# v1.net
KiCad netlist of a schematic drawn in EAGLE
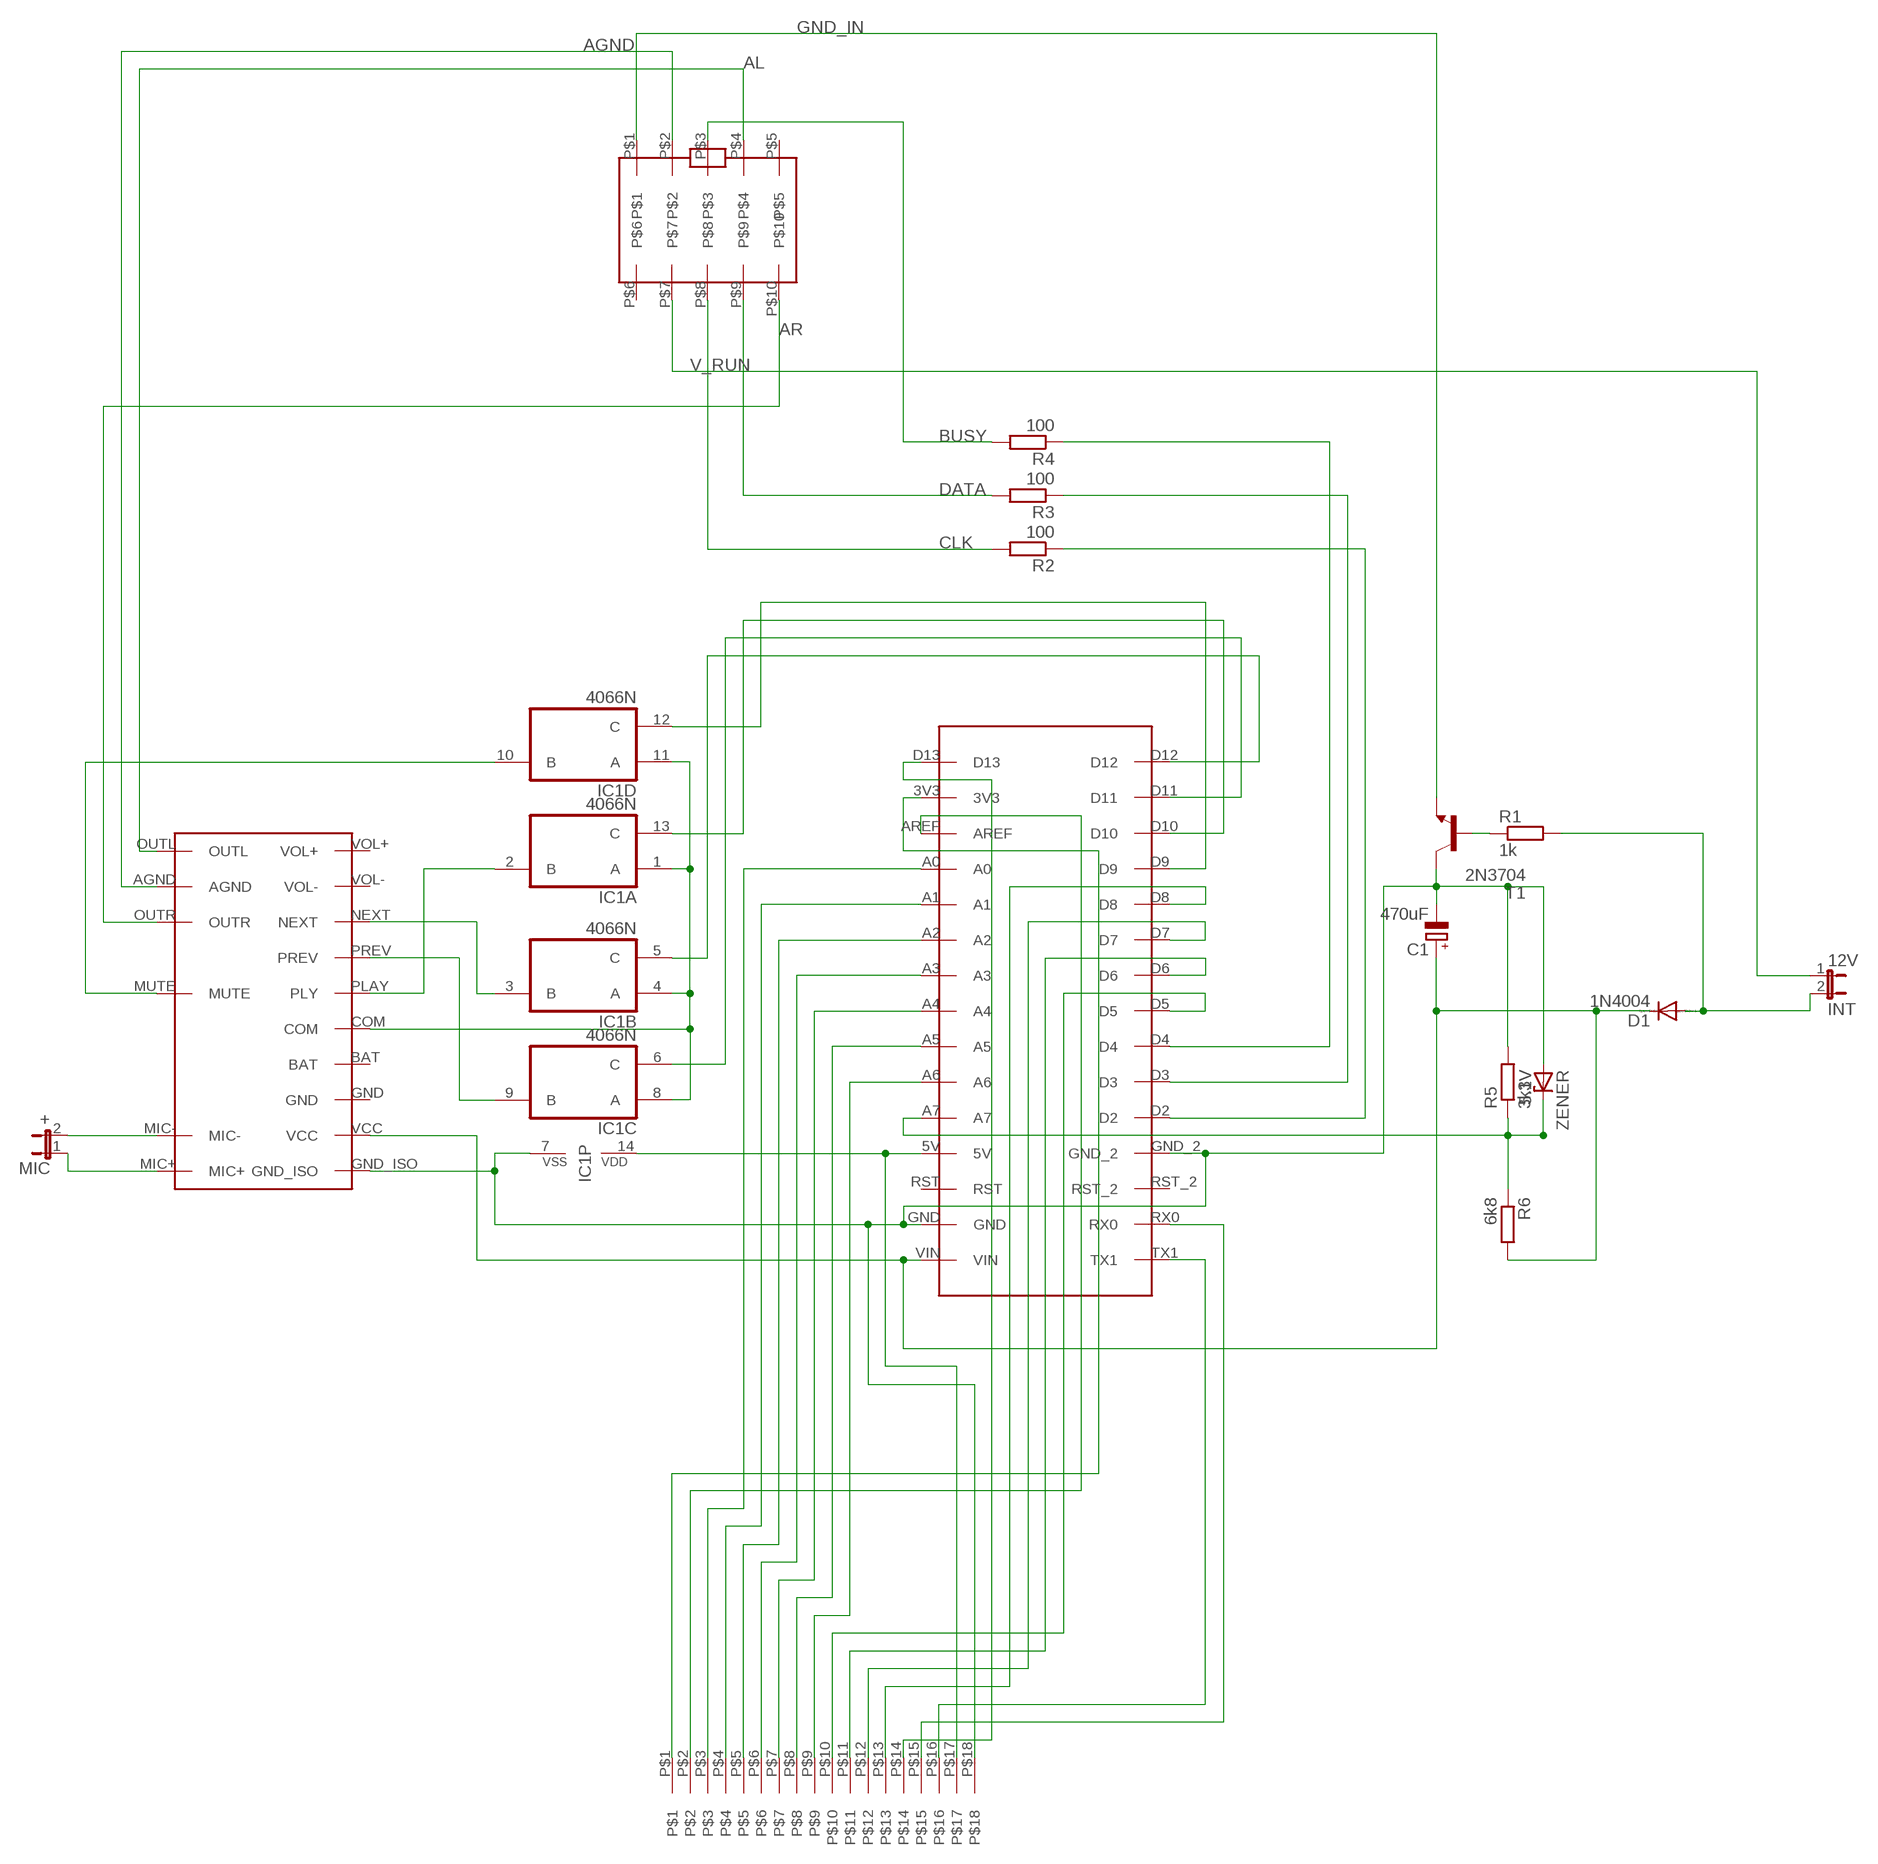
[diagram p0: schematic, sheet 1]

(export (version "E")
  (design (tool "Eeschema 10.0.6"))
  (components
    (comp (ref "12V")
      (value "INT")
      (footprint "eagle-import:JP1")
      (libsource (lib "eagle-import") (part "JP1E"))
    )
    (comp (ref "C1")
      (value "470uF")
      (footprint "eagle-import:E3,5-8")
      (libsource (lib "eagle-import") (part "CPOL-EUE3.5-8"))
    )
    (comp (ref "D1")
      (value "1N4004")
      (footprint "eagle-import:DO41-10")
      (libsource (lib "eagle-import") (part "1N4004"))
    )
    (comp (ref "IC1")
      (value "4066N")
      (footprint "eagle-import:DIL14")
      (libsource (lib "eagle-import") (part "4066N"))
    )
    (comp (ref "MIC")
      (value "+")
      (footprint "eagle-import:JP1")
      (libsource (lib "eagle-import") (part "JP1E"))
    )
    (comp (ref "R1")
      (value "1k")
      (footprint "eagle-import:0207_10")
      (libsource (lib "eagle-import") (part "R-EU_0207/10"))
    )
    (comp (ref "R2")
      (value "100")
      (footprint "eagle-import:0207_10")
      (libsource (lib "eagle-import") (part "R-EU_0207/10"))
    )
    (comp (ref "R3")
      (value "100")
      (footprint "eagle-import:0207_10")
      (libsource (lib "eagle-import") (part "R-EU_0207/10"))
    )
    (comp (ref "R4")
      (value "100")
      (footprint "eagle-import:0207_10")
      (libsource (lib "eagle-import") (part "R-EU_0207/10"))
    )
    (comp (ref "R5")
      (value "3k3")
      (footprint "eagle-import:0207_10")
      (libsource (lib "eagle-import") (part "R-EU_0207/10"))
    )
    (comp (ref "R6")
      (value "6k8")
      (footprint "eagle-import:0207_10")
      (libsource (lib "eagle-import") (part "R-EU_0207/10"))
    )
    (comp (ref "T1")
      (value "2N3704")
      (footprint "eagle-import:TO92")
      (libsource (lib "eagle-import") (part "2N3704"))
    )
    (comp (ref "U$1")
      (value "JMP18X1")
      (footprint "eagle-import:JMP18X1")
      (libsource (lib "eagle-import") (part "JMP18X1"))
    )
    (comp (ref "U$2")
      (value "CSR8645_MODULE")
      (footprint "eagle-import:CSR8645_MODULE")
      (libsource (lib "eagle-import") (part "CSR8645_MODULE"))
    )
    (comp (ref "U$4")
      (value "2X5_PIN_SOCKET")
      (footprint "eagle-import:2X5_PIN_SOCKET")
      (libsource (lib "eagle-import") (part "2X5_PIN_SOCKET"))
    )
    (comp (ref "U$5")
      (value "ARDUINO_NANO")
      (footprint "eagle-import:ARDUINO_NANO")
      (libsource (lib "eagle-import") (part "ARDUINO_NANO"))
    )
    (comp (ref "ZENER")
      (value "5.1V")
      (footprint "eagle-import:DO41Z10")
      (libsource (lib "eagle-import") (part "ZENER-DIODEDO41Z10"))
    )
  )
  (nets
    (net (code "1") (name "/AGND") (class "Default")
      (node (ref "U$2") (pin "AGND") (pinfunction "AGND_AGND") (pintype "bidirectional"))
      (node (ref "U$4") (pin "P$2") (pinfunction "P$2_P$2") (pintype "bidirectional"))
    )
    (net (code "2") (name "/AL") (class "Default")
      (node (ref "U$2") (pin "OUTL") (pinfunction "OUTL_OUTL") (pintype "bidirectional"))
      (node (ref "U$4") (pin "P$4") (pinfunction "P$4_P$4") (pintype "bidirectional"))
    )
    (net (code "3") (name "/AR") (class "Default")
      (node (ref "U$2") (pin "OUTR") (pinfunction "OUTR_OUTR") (pintype "bidirectional"))
      (node (ref "U$4") (pin "P$10") (pinfunction "P$10_P$10") (pintype "bidirectional"))
    )
    (net (code "4") (name "/BUSY") (class "Default")
      (node (ref "R4") (pin "2") (pinfunction "2_2") (pintype "passive"))
      (node (ref "U$4") (pin "P$3") (pinfunction "P$3_P$3") (pintype "bidirectional"))
    )
    (net (code "5") (name "/CLK") (class "Default")
      (node (ref "R2") (pin "2") (pinfunction "2_2") (pintype "passive"))
      (node (ref "U$4") (pin "P$8") (pinfunction "P$8_P$8") (pintype "bidirectional"))
    )
    (net (code "6") (name "/DATA") (class "Default")
      (node (ref "R3") (pin "2") (pinfunction "2_2") (pintype "passive"))
      (node (ref "U$4") (pin "P$9") (pinfunction "P$9_P$9") (pintype "bidirectional"))
    )
    (net (code "7") (name "/GND_IN") (class "Default")
      (node (ref "T1") (pin "3") (pinfunction "E_3") (pintype "passive"))
      (node (ref "U$4") (pin "P$1") (pinfunction "P$1_P$1") (pintype "bidirectional"))
    )
    (net (code "8") (name "/V_RUN") (class "Default")
      (node (ref "12V") (pin "1") (pinfunction "1_1") (pintype "passive"))
      (node (ref "U$4") (pin "P$7") (pinfunction "P$7_P$7") (pintype "bidirectional"))
    )
    (net (code "9") (name "Net-(12V-Pad2)") (class "Default")
      (node (ref "12V") (pin "2") (pinfunction "2_2") (pintype "passive"))
      (node (ref "D1") (pin "A") (pinfunction "A_A") (pintype "passive"))
      (node (ref "R1") (pin "2") (pinfunction "2_2") (pintype "passive"))
    )
    (net (code "10") (name "Net-(C1-Pad+)") (class "Default")
      (node (ref "C1") (pin "+") (pinfunction "+_+") (pintype "passive"))
      (node (ref "D1") (pin "C") (pinfunction "C_C") (pintype "passive"))
      (node (ref "R6") (pin "2") (pinfunction "2_2") (pintype "passive"))
      (node (ref "U$2") (pin "VCC") (pinfunction "VCC_VCC") (pintype "bidirectional"))
      (node (ref "U$5") (pin "VIN") (pinfunction "VIN_VIN") (pintype "power_in"))
    )
    (net (code "11") (name "Net-(IC1A-A)") (class "Default")
      (node (ref "IC1") (pin "1") (pinfunction "A_1") (pintype "tri_state"))
      (node (ref "IC1") (pin "11") (pinfunction "A_11") (pintype "tri_state"))
      (node (ref "IC1") (pin "4") (pinfunction "A_4") (pintype "tri_state"))
      (node (ref "IC1") (pin "8") (pinfunction "A_8") (pintype "tri_state"))
      (node (ref "U$2") (pin "COM") (pinfunction "COM_COM") (pintype "bidirectional"))
    )
    (net (code "12") (name "Net-(IC1A-B)") (class "Default")
      (node (ref "IC1") (pin "2") (pinfunction "B_2") (pintype "tri_state"))
      (node (ref "U$2") (pin "PLAY") (pinfunction "PLY_PLAY") (pintype "bidirectional"))
    )
    (net (code "13") (name "Net-(IC1A-C)") (class "Default")
      (node (ref "IC1") (pin "13") (pinfunction "C_13") (pintype "input"))
      (node (ref "U$5") (pin "D10") (pinfunction "D10_D10") (pintype "bidirectional"))
    )
    (net (code "14") (name "Net-(IC1B-B)") (class "Default")
      (node (ref "IC1") (pin "3") (pinfunction "B_3") (pintype "tri_state"))
      (node (ref "U$2") (pin "NEXT") (pinfunction "NEXT_NEXT") (pintype "bidirectional"))
    )
    (net (code "15") (name "Net-(IC1B-C)") (class "Default")
      (node (ref "IC1") (pin "5") (pinfunction "C_5") (pintype "input"))
      (node (ref "U$5") (pin "D12") (pinfunction "D12_D12") (pintype "bidirectional"))
    )
    (net (code "16") (name "Net-(IC1C-B)") (class "Default")
      (node (ref "IC1") (pin "9") (pinfunction "B_9") (pintype "tri_state"))
      (node (ref "U$2") (pin "PREV") (pinfunction "PREV_PREV") (pintype "bidirectional"))
    )
    (net (code "17") (name "Net-(IC1C-C)") (class "Default")
      (node (ref "IC1") (pin "6") (pinfunction "C_6") (pintype "input"))
      (node (ref "U$5") (pin "D11") (pinfunction "D11_D11") (pintype "bidirectional"))
    )
    (net (code "18") (name "Net-(IC1D-B)") (class "Default")
      (node (ref "IC1") (pin "10") (pinfunction "B_10") (pintype "tri_state"))
      (node (ref "U$2") (pin "MUTE") (pinfunction "MUTE_MUTE") (pintype "bidirectional"))
    )
    (net (code "19") (name "Net-(IC1D-C)") (class "Default")
      (node (ref "IC1") (pin "12") (pinfunction "C_12") (pintype "input"))
      (node (ref "U$5") (pin "D9") (pinfunction "D9_D9") (pintype "bidirectional"))
    )
    (net (code "20") (name "Net-(IC1E-VDD)") (class "Default")
      (node (ref "IC1") (pin "14") (pinfunction "VDD_14") (pintype "power_in"))
      (node (ref "U$1") (pin "P$17") (pinfunction "P$17_P$17") (pintype "bidirectional"))
      (node (ref "U$5") (pin "5V") (pinfunction "5V_5V") (pintype "bidirectional"))
    )
    (net (code "21") (name "Net-(IC1E-VSS)") (class "Default")
      (node (ref "C1") (pin "-") (pinfunction "-_-") (pintype "passive"))
      (node (ref "IC1") (pin "7") (pinfunction "VSS_7") (pintype "power_in"))
      (node (ref "R5") (pin "2") (pinfunction "2_2") (pintype "passive"))
      (node (ref "T1") (pin "2") (pinfunction "C_2") (pintype "passive"))
      (node (ref "U$1") (pin "P$18") (pinfunction "P$18_P$18") (pintype "bidirectional"))
      (node (ref "U$2") (pin "GND_ISO") (pinfunction "GND_ISO_GND_ISO") (pintype "bidirectional"))
      (node (ref "U$5") (pin "GND") (pinfunction "GND_GND") (pintype "power_in"))
      (node (ref "U$5") (pin "GND_2") (pinfunction "GND_2_GND_2") (pintype "power_in"))
      (node (ref "ZENER") (pin "A") (pinfunction "A_A") (pintype "passive"))
    )
    (net (code "22") (name "Net-(MIC-Pad1)") (class "Default")
      (node (ref "MIC") (pin "1") (pinfunction "1_1") (pintype "passive"))
      (node (ref "U$2") (pin "MIC+") (pinfunction "MIC+_MIC+") (pintype "bidirectional"))
    )
    (net (code "23") (name "Net-(MIC-Pad2)") (class "Default")
      (node (ref "MIC") (pin "2") (pinfunction "2_2") (pintype "passive"))
      (node (ref "U$2") (pin "MIC-") (pinfunction "MIC-_MIC-") (pintype "bidirectional"))
    )
    (net (code "24") (name "Net-(R2-Pad1)") (class "Default")
      (node (ref "R2") (pin "1") (pinfunction "1_1") (pintype "passive"))
      (node (ref "U$5") (pin "D2") (pinfunction "D2_D2") (pintype "bidirectional"))
    )
    (net (code "25") (name "Net-(R3-Pad1)") (class "Default")
      (node (ref "R3") (pin "1") (pinfunction "1_1") (pintype "passive"))
      (node (ref "U$5") (pin "D3") (pinfunction "D3_D3") (pintype "bidirectional"))
    )
    (net (code "26") (name "Net-(R4-Pad1)") (class "Default")
      (node (ref "R4") (pin "1") (pinfunction "1_1") (pintype "passive"))
      (node (ref "U$5") (pin "D4") (pinfunction "D4_D4") (pintype "bidirectional"))
    )
    (net (code "27") (name "Net-(R5-Pad1)") (class "Default")
      (node (ref "R5") (pin "1") (pinfunction "1_1") (pintype "passive"))
      (node (ref "R6") (pin "1") (pinfunction "1_1") (pintype "passive"))
      (node (ref "U$5") (pin "A7") (pinfunction "A7_A7") (pintype "bidirectional"))
      (node (ref "ZENER") (pin "C") (pinfunction "C_C") (pintype "passive"))
    )
    (net (code "28") (name "Net-(T1-B)") (class "Default")
      (node (ref "R1") (pin "1") (pinfunction "1_1") (pintype "passive"))
      (node (ref "T1") (pin "1") (pinfunction "B_1") (pintype "passive"))
    )
    (net (code "29") (name "Net-(U$1-PadP$1)") (class "Default")
      (node (ref "U$1") (pin "P$1") (pinfunction "P$1_P$1") (pintype "bidirectional"))
      (node (ref "U$5") (pin "3V3") (pinfunction "3V3_3V3") (pintype "bidirectional"))
    )
    (net (code "30") (name "Net-(U$1-PadP$2)") (class "Default")
      (node (ref "U$1") (pin "P$2") (pinfunction "P$2_P$2") (pintype "bidirectional"))
      (node (ref "U$5") (pin "AREF") (pinfunction "AREF_AREF") (pintype "bidirectional"))
    )
    (net (code "31") (name "Net-(U$1-PadP$3)") (class "Default")
      (node (ref "U$1") (pin "P$3") (pinfunction "P$3_P$3") (pintype "bidirectional"))
      (node (ref "U$5") (pin "A0") (pinfunction "A0_A0") (pintype "bidirectional"))
    )
    (net (code "32") (name "Net-(U$1-PadP$4)") (class "Default")
      (node (ref "U$1") (pin "P$4") (pinfunction "P$4_P$4") (pintype "bidirectional"))
      (node (ref "U$5") (pin "A1") (pinfunction "A1_A1") (pintype "bidirectional"))
    )
    (net (code "33") (name "Net-(U$1-PadP$5)") (class "Default")
      (node (ref "U$1") (pin "P$5") (pinfunction "P$5_P$5") (pintype "bidirectional"))
      (node (ref "U$5") (pin "A2") (pinfunction "A2_A2") (pintype "bidirectional"))
    )
    (net (code "34") (name "Net-(U$1-PadP$6)") (class "Default")
      (node (ref "U$1") (pin "P$6") (pinfunction "P$6_P$6") (pintype "bidirectional"))
      (node (ref "U$5") (pin "A3") (pinfunction "A3_A3") (pintype "bidirectional"))
    )
    (net (code "35") (name "Net-(U$1-PadP$7)") (class "Default")
      (node (ref "U$1") (pin "P$7") (pinfunction "P$7_P$7") (pintype "bidirectional"))
      (node (ref "U$5") (pin "A4") (pinfunction "A4_A4") (pintype "bidirectional"))
    )
    (net (code "36") (name "Net-(U$1-PadP$8)") (class "Default")
      (node (ref "U$1") (pin "P$8") (pinfunction "P$8_P$8") (pintype "bidirectional"))
      (node (ref "U$5") (pin "A5") (pinfunction "A5_A5") (pintype "bidirectional"))
    )
    (net (code "37") (name "Net-(U$1-PadP$9)") (class "Default")
      (node (ref "U$1") (pin "P$9") (pinfunction "P$9_P$9") (pintype "bidirectional"))
      (node (ref "U$5") (pin "A6") (pinfunction "A6_A6") (pintype "bidirectional"))
    )
    (net (code "38") (name "Net-(U$1-PadP$10)") (class "Default")
      (node (ref "U$1") (pin "P$10") (pinfunction "P$10_P$10") (pintype "bidirectional"))
      (node (ref "U$5") (pin "D5") (pinfunction "D5_D5") (pintype "bidirectional"))
    )
    (net (code "39") (name "Net-(U$1-PadP$11)") (class "Default")
      (node (ref "U$1") (pin "P$11") (pinfunction "P$11_P$11") (pintype "bidirectional"))
      (node (ref "U$5") (pin "D6") (pinfunction "D6_D6") (pintype "bidirectional"))
    )
    (net (code "40") (name "Net-(U$1-PadP$12)") (class "Default")
      (node (ref "U$1") (pin "P$12") (pinfunction "P$12_P$12") (pintype "bidirectional"))
      (node (ref "U$5") (pin "D7") (pinfunction "D7_D7") (pintype "bidirectional"))
    )
    (net (code "41") (name "Net-(U$1-PadP$13)") (class "Default")
      (node (ref "U$1") (pin "P$13") (pinfunction "P$13_P$13") (pintype "bidirectional"))
      (node (ref "U$5") (pin "D8") (pinfunction "D8_D8") (pintype "bidirectional"))
    )
    (net (code "42") (name "Net-(U$1-PadP$14)") (class "Default")
      (node (ref "U$1") (pin "P$14") (pinfunction "P$14_P$14") (pintype "bidirectional"))
      (node (ref "U$5") (pin "D13") (pinfunction "D13_D13") (pintype "bidirectional"))
    )
    (net (code "43") (name "Net-(U$1-PadP$15)") (class "Default")
      (node (ref "U$1") (pin "P$15") (pinfunction "P$15_P$15") (pintype "bidirectional"))
      (node (ref "U$5") (pin "RX0") (pinfunction "RX0_RX0") (pintype "bidirectional"))
    )
    (net (code "44") (name "Net-(U$1-PadP$16)") (class "Default")
      (node (ref "U$1") (pin "P$16") (pinfunction "P$16_P$16") (pintype "bidirectional"))
      (node (ref "U$5") (pin "TX1") (pinfunction "TX1_TX1") (pintype "bidirectional"))
    )
    (net (code "45") (name "unconnected-(U$2-PadBAT)") (class "Default")
      (node (ref "U$2") (pin "BAT") (pinfunction "BAT_BAT") (pintype "bidirectional"))
    )
    (net (code "46") (name "unconnected-(U$2-PadGND)") (class "Default")
      (node (ref "U$2") (pin "GND") (pinfunction "GND_GND") (pintype "bidirectional"))
    )
    (net (code "47") (name "unconnected-(U$2-PadVOL+)") (class "Default")
      (node (ref "U$2") (pin "VOL+") (pinfunction "VOL+_VOL+") (pintype "bidirectional"))
    )
    (net (code "48") (name "unconnected-(U$2-PadVOL-)") (class "Default")
      (node (ref "U$2") (pin "VOL-") (pinfunction "VOL-_VOL-") (pintype "bidirectional"))
    )
    (net (code "49") (name "unconnected-(U$4-PadP$5)") (class "Default")
      (node (ref "U$4") (pin "P$5") (pinfunction "P$5_P$5") (pintype "bidirectional"))
    )
    (net (code "50") (name "unconnected-(U$4-PadP$6)") (class "Default")
      (node (ref "U$4") (pin "P$6") (pinfunction "P$6_P$6") (pintype "bidirectional"))
    )
    (net (code "51") (name "unconnected-(U$5-PadRST)") (class "Default")
      (node (ref "U$5") (pin "RST") (pinfunction "RST_RST") (pintype "bidirectional"))
    )
    (net (code "52") (name "unconnected-(U$5-PadRST_2)") (class "Default")
      (node (ref "U$5") (pin "RST_2") (pinfunction "RST_2_RST_2") (pintype "bidirectional"))
    )
  )
)
